# 7I92ETH.net
KiCad netlist of a schematic drawn in Altium Designer
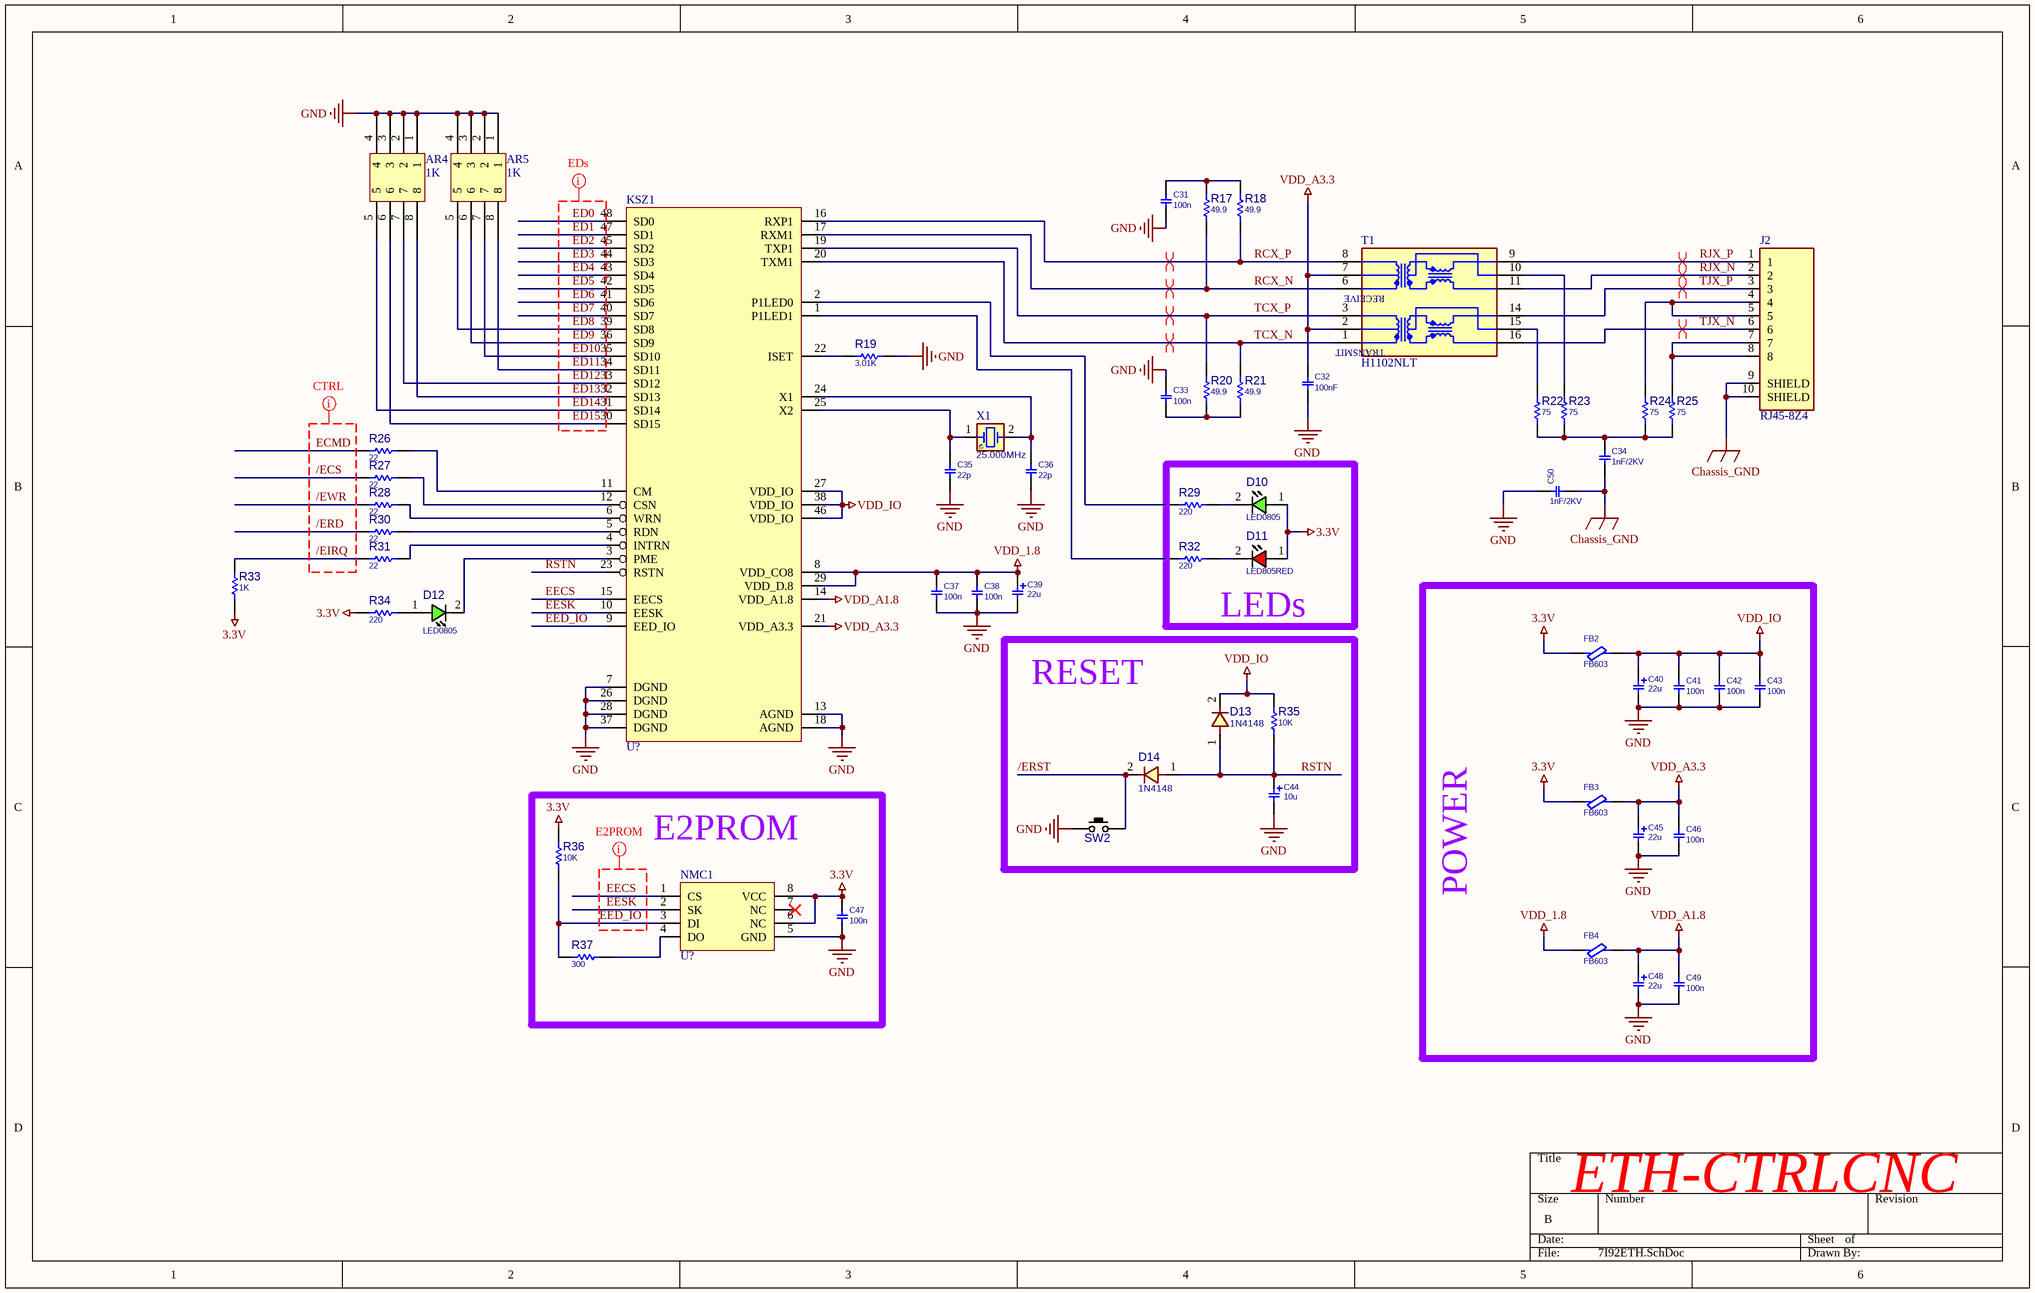
[diagram p0: 7I92ETH.SchDoc]

(export (version "E")
  (design (tool "Eeschema 10.0.6"))
  (components
    (comp (ref "AR4") (value "1K") (footprint "RP0603X4") (libsource (lib "Full_libraries") (part "ARRAY*4")))
    (comp (ref "AR5") (value "1K") (footprint "RP0603X4") (libsource (lib "Full_libraries") (part "ARRAY*4")))
    (comp (ref "C31")
      (value "100n")
      (footprint "C0603")
      (description "CAP, MLCC, 1nF, 50V, C0G, 10%, 0402")
      (fields (field (name "MANF") "Murata"))
      (libsource (lib "Full_libraries") (part "CAP_SMD_MLCC"))
    )
    (comp (ref "C32")
      (value "100nF")
      (footprint "C0603")
      (description "CAP, MLCC, 1nF, 50V, C0G, 10%, 0402")
      (fields (field (name "MANF") "Murata"))
      (libsource (lib "Full_libraries") (part "CAP_SMD_MLCC"))
    )
    (comp (ref "C33")
      (value "100n")
      (footprint "C0603")
      (description "CAP, MLCC, 1nF, 50V, C0G, 10%, 0402")
      (fields (field (name "MANF") "Murata"))
      (libsource (lib "Full_libraries") (part "CAP_SMD_MLCC"))
    )
    (comp (ref "C34")
      (value "1nF/2KV")
      (footprint "C1812")
      (description "CAP, MLCC, 1nF, 50V, C0G, 10%, 0402")
      (fields (field (name "MANF") "Murata"))
      (libsource (lib "Full_libraries") (part "CAP_SMD_MLCC"))
    )
    (comp (ref "C35")
      (value "22p")
      (footprint "C0603")
      (description "CAP, MLCC, 1nF, 50V, C0G, 10%, 0402")
      (fields (field (name "MANF") "Murata"))
      (libsource (lib "Full_libraries") (part "CAP_SMD_MLCC"))
    )
    (comp (ref "C36")
      (value "22p")
      (footprint "C0603")
      (description "CAP, MLCC, 1nF, 50V, C0G, 10%, 0402")
      (fields (field (name "MANF") "Murata"))
      (libsource (lib "Full_libraries") (part "CAP_SMD_MLCC"))
    )
    (comp (ref "C37")
      (value "100n")
      (footprint "C0603")
      (description "CAP, MLCC, 1nF, 50V, C0G, 10%, 0402")
      (fields (field (name "MANF") "Murata"))
      (libsource (lib "Full_libraries") (part "CAP_SMD_MLCC"))
    )
    (comp (ref "C38")
      (value "100n")
      (footprint "C0603")
      (description "CAP, MLCC, 1nF, 50V, C0G, 10%, 0402")
      (fields (field (name "MANF") "Murata"))
      (libsource (lib "Full_libraries") (part "CAP_SMD_MLCC"))
    )
    (comp (ref "C39")
      (value "22u")
      (footprint "C_TN_3216")
      (description "CAP, SMD, TAN,")
      (libsource (lib "Full_libraries") (part "CAP_SMD_TAN"))
    )
    (comp (ref "C40")
      (value "22u")
      (footprint "C_TN_3216")
      (description "CAP, SMD, TAN,")
      (libsource (lib "Full_libraries") (part "CAP_SMD_TAN"))
    )
    (comp (ref "C41")
      (value "100n")
      (footprint "C0603")
      (description "CAP, MLCC, 1nF, 50V, C0G, 10%, 0402")
      (fields (field (name "MANF") "Murata"))
      (libsource (lib "Full_libraries") (part "CAP_SMD_MLCC"))
    )
    (comp (ref "C42")
      (value "100n")
      (footprint "C0603")
      (description "CAP, MLCC, 1nF, 50V, C0G, 10%, 0402")
      (fields (field (name "MANF") "Murata"))
      (libsource (lib "Full_libraries") (part "CAP_SMD_MLCC"))
    )
    (comp (ref "C43")
      (value "100n")
      (footprint "C0603")
      (description "CAP, MLCC, 1nF, 50V, C0G, 10%, 0402")
      (fields (field (name "MANF") "Murata"))
      (libsource (lib "Full_libraries") (part "CAP_SMD_MLCC"))
    )
    (comp (ref "C44")
      (value "10u")
      (footprint "C_TN_3216")
      (description "CAP, SMD, TAN,")
      (libsource (lib "Full_libraries") (part "CAP_SMD_TAN"))
    )
    (comp (ref "C45")
      (value "22u")
      (footprint "C_TN_3216")
      (description "CAP, SMD, TAN,")
      (libsource (lib "Full_libraries") (part "CAP_SMD_TAN"))
    )
    (comp (ref "C46")
      (value "100n")
      (footprint "C0603")
      (description "CAP, MLCC, 1nF, 50V, C0G, 10%, 0402")
      (fields (field (name "MANF") "Murata"))
      (libsource (lib "Full_libraries") (part "CAP_SMD_MLCC"))
    )
    (comp (ref "C47")
      (value "100n")
      (footprint "C0603")
      (description "CAP, MLCC, 1nF, 50V, C0G, 10%, 0402")
      (fields (field (name "MANF") "Murata"))
      (libsource (lib "Full_libraries") (part "CAP_SMD_MLCC"))
    )
    (comp (ref "C48")
      (value "22u")
      (footprint "C_TN_3216")
      (description "CAP, SMD, TAN,")
      (libsource (lib "Full_libraries") (part "CAP_SMD_TAN"))
    )
    (comp (ref "C49")
      (value "100n")
      (footprint "C0603")
      (description "CAP, MLCC, 1nF, 50V, C0G, 10%, 0402")
      (fields (field (name "MANF") "Murata"))
      (libsource (lib "Full_libraries") (part "CAP_SMD_MLCC"))
    )
    (comp (ref "C50")
      (value "1nF/2KV")
      (footprint "C1812")
      (description "CAP, MLCC, 1nF, 50V, C0G, 10%, 0402")
      (fields (field (name "MANF") "Murata"))
      (libsource (lib "Full_libraries") (part "CAP_SMD_MLCC"))
    )
    (comp (ref "D10")
      (value "LED0805")
      (footprint "LED0805")
      (description "LED, SMD, 0805")
      (fields (field (name "MANF") "MANF") (field (name "MANF_P#") "MANF_PART#"))
      (libsource (lib "Full_libraries") (part "LED_SMD_0805"))
    )
    (comp (ref "D11")
      (value "LED805RED")
      (footprint "LED0805RED")
      (description "LED, SMD, 0805, RED")
      (fields (field (name "MANF") "MANF") (field (name "MANF_P#") "MANF_PART#"))
      (libsource (lib "Full_libraries") (part "LED_SMD_0805_RED"))
    )
    (comp (ref "D12")
      (value "LED0805")
      (footprint "LED0805")
      (description "LED, SMD, 0805")
      (fields (field (name "MANF") "MANF") (field (name "MANF_P#") "MANF_PART#"))
      (libsource (lib "Full_libraries") (part "LED_SMD_0805"))
    )
    (comp (ref "D13")
      (value "1N4148")
      (footprint "D_SOD80")
      (description "DIODE, FAST SWTICHING, 0.3A, 0.5W")
      (fields (field (name "MANF") "MANF"))
      (libsource (lib "Full_libraries") (part "DIODE_SMD_1N4148"))
    )
    (comp (ref "D14")
      (value "1N4148")
      (footprint "D_SOD80")
      (description "DIODE, FAST SWTICHING, 0.3A, 0.5W")
      (fields (field (name "MANF") "MANF"))
      (libsource (lib "Full_libraries") (part "DIODE_SMD_1N4148"))
    )
    (comp (ref "FB2")
      (value "FB603")
      (footprint "L1206")
      (description "FERRITE_Bead, SMD")
      (fields (field (name "MANF") "MURATA") (field (name "MANF_P#") "BLM15AG121SN1D"))
      (libsource (lib "Full_libraries") (part "FBEAD_SMD"))
    )
    (comp (ref "FB3")
      (value "FB603")
      (footprint "L1206")
      (description "FERRITE_Bead, SMD")
      (fields (field (name "MANF") "MURATA") (field (name "MANF_P#") "BLM15AG121SN1D"))
      (libsource (lib "Full_libraries") (part "FBEAD_SMD"))
    )
    (comp (ref "FB4")
      (value "FB603")
      (footprint "L1206")
      (description "FERRITE_Bead, SMD")
      (fields (field (name "MANF") "MURATA") (field (name "MANF_P#") "BLM15AG121SN1D"))
      (libsource (lib "Full_libraries") (part "FBEAD_SMD"))
    )
    (comp (ref "J2")
      (value "RJ45-8Z4")
      (footprint "TE_RJ45-8Z4")
      (description "CONN MOD JACK 8P8C R/A SHIELDED")
      (fields (field (name "MF") "{'manufacturer': u'TE Connectivity'}"))
      (libsource (lib "SnapEDA_Library") (part "RJ45-8Z4"))
    )
    (comp (ref "KSZ1")
      (value "U?")
      (footprint "QFG50_48")
      (description "ETHERNET IC")
      (libsource (lib "Ethernet_7i92_SchLib") (part "KSZ8851"))
    )
    (comp (ref "NMC1")
      (value "U?")
      (footprint "SO_8")
      (description "1024 BYTE ERASABLE PROGRAMABLE MEMORY")
      (libsource (lib "Ethernet_7i92_SchLib") (part "NMC9346"))
    )
    (comp (ref "R17")
      (value "49.9")
      (footprint "R0603")
      (description "RESISTOR, SMD")
      (fields (field (name "MANF_P#") "RK73H1ETTP4701F") (field (name "MANF") "KOA SPEER"))
      (libsource (lib "Full_libraries") (part "RES_SMD"))
    )
    (comp (ref "R18")
      (value "49.9")
      (footprint "R0603")
      (description "RESISTOR, SMD")
      (fields (field (name "MANF_P#") "RK73H1ETTP4701F") (field (name "MANF") "KOA SPEER"))
      (libsource (lib "Full_libraries") (part "RES_SMD"))
    )
    (comp (ref "R19")
      (value "3.01K")
      (footprint "R0805")
      (description "RESISTOR, SMD")
      (fields (field (name "MANF_P#") "RK73H1ETTP4701F") (field (name "MANF") "KOA SPEER"))
      (libsource (lib "Full_libraries") (part "RES_SMD"))
    )
    (comp (ref "R20")
      (value "49.9")
      (footprint "R0603")
      (description "RESISTOR, SMD")
      (fields (field (name "MANF_P#") "RK73H1ETTP4701F") (field (name "MANF") "KOA SPEER"))
      (libsource (lib "Full_libraries") (part "RES_SMD"))
    )
    (comp (ref "R21")
      (value "49.9")
      (footprint "R0603")
      (description "RESISTOR, SMD")
      (fields (field (name "MANF_P#") "RK73H1ETTP4701F") (field (name "MANF") "KOA SPEER"))
      (libsource (lib "Full_libraries") (part "RES_SMD"))
    )
    (comp (ref "R22")
      (value "75")
      (footprint "R0805")
      (description "RESISTOR, SMD")
      (fields (field (name "MANF_P#") "RK73H1ETTP4701F") (field (name "MANF") "KOA SPEER"))
      (libsource (lib "Full_libraries") (part "RES_SMD"))
    )
    (comp (ref "R23")
      (value "75")
      (footprint "R0805")
      (description "RESISTOR, SMD")
      (fields (field (name "MANF_P#") "RK73H1ETTP4701F") (field (name "MANF") "KOA SPEER"))
      (libsource (lib "Full_libraries") (part "RES_SMD"))
    )
    (comp (ref "R24")
      (value "75")
      (footprint "R0805")
      (description "RESISTOR, SMD")
      (fields (field (name "MANF_P#") "RK73H1ETTP4701F") (field (name "MANF") "KOA SPEER"))
      (libsource (lib "Full_libraries") (part "RES_SMD"))
    )
    (comp (ref "R25")
      (value "75")
      (footprint "R0805")
      (description "RESISTOR, SMD")
      (fields (field (name "MANF_P#") "RK73H1ETTP4701F") (field (name "MANF") "KOA SPEER"))
      (libsource (lib "Full_libraries") (part "RES_SMD"))
    )
    (comp (ref "R26")
      (value "22")
      (footprint "R0603")
      (description "RESISTOR, SMD")
      (fields (field (name "MANF_P#") "RK73H1ETTP4701F") (field (name "MANF") "KOA SPEER"))
      (libsource (lib "Full_libraries") (part "RES_SMD"))
    )
    (comp (ref "R27")
      (value "22")
      (footprint "R0603")
      (description "RESISTOR, SMD")
      (fields (field (name "MANF_P#") "RK73H1ETTP4701F") (field (name "MANF") "KOA SPEER"))
      (libsource (lib "Full_libraries") (part "RES_SMD"))
    )
    (comp (ref "R28")
      (value "22")
      (footprint "R0603")
      (description "RESISTOR, SMD")
      (fields (field (name "MANF_P#") "RK73H1ETTP4701F") (field (name "MANF") "KOA SPEER"))
      (libsource (lib "Full_libraries") (part "RES_SMD"))
    )
    (comp (ref "R29")
      (value "220")
      (footprint "R0805")
      (description "RESISTOR, SMD")
      (fields (field (name "MANF_P#") "RK73H1ETTP4701F") (field (name "MANF") "KOA SPEER"))
      (libsource (lib "Full_libraries") (part "RES_SMD"))
    )
    (comp (ref "R30")
      (value "22")
      (footprint "R0603")
      (description "RESISTOR, SMD")
      (fields (field (name "MANF_P#") "RK73H1ETTP4701F") (field (name "MANF") "KOA SPEER"))
      (libsource (lib "Full_libraries") (part "RES_SMD"))
    )
    (comp (ref "R31")
      (value "22")
      (footprint "R0603")
      (description "RESISTOR, SMD")
      (fields (field (name "MANF_P#") "RK73H1ETTP4701F") (field (name "MANF") "KOA SPEER"))
      (libsource (lib "Full_libraries") (part "RES_SMD"))
    )
    (comp (ref "R32")
      (value "220")
      (footprint "R0805")
      (description "RESISTOR, SMD")
      (fields (field (name "MANF_P#") "RK73H1ETTP4701F") (field (name "MANF") "KOA SPEER"))
      (libsource (lib "Full_libraries") (part "RES_SMD"))
    )
    (comp (ref "R33")
      (value "1K")
      (footprint "R0603")
      (description "RESISTOR, SMD")
      (fields (field (name "MANF_P#") "RK73H1ETTP4701F") (field (name "MANF") "KOA SPEER"))
      (libsource (lib "Full_libraries") (part "RES_SMD"))
    )
    (comp (ref "R34")
      (value "220")
      (footprint "R0603")
      (description "RESISTOR, SMD")
      (fields (field (name "MANF_P#") "RK73H1ETTP4701F") (field (name "MANF") "KOA SPEER"))
      (libsource (lib "Full_libraries") (part "RES_SMD"))
    )
    (comp (ref "R35")
      (value "10K")
      (footprint "R0603")
      (description "RESISTOR, SMD")
      (fields (field (name "MANF_P#") "RK73H1ETTP4701F") (field (name "MANF") "KOA SPEER"))
      (libsource (lib "Full_libraries") (part "RES_SMD"))
    )
    (comp (ref "R36")
      (value "10K")
      (footprint "R0603")
      (description "RESISTOR, SMD")
      (fields (field (name "MANF_P#") "RK73H1ETTP4701F") (field (name "MANF") "KOA SPEER"))
      (libsource (lib "Full_libraries") (part "RES_SMD"))
    )
    (comp (ref "R37")
      (value "300")
      (footprint "R0603")
      (description "RESISTOR, SMD")
      (fields (field (name "MANF_P#") "RK73H1ETTP4701F") (field (name "MANF") "KOA SPEER"))
      (libsource (lib "Full_libraries") (part "RES_SMD"))
    )
    (comp (ref "SW2")
      (value "PUSHBUTTON")
      (footprint "SWPBS_SPST_6X3X5")
      (description "SWITCH, PUSH BUTTON, TACTILE, SMD, SPST, 6X3.5X4.3mm")
      (fields (field (name "MANF") "Panasonic") (field (name "MANF_P#") "EVQ-PNF04M"))
      (libsource (lib "Full_libraries") (part "SWPBS_SPST_6X3X4"))
    )
    (comp (ref "T1")
      (value "H1102NLT")
      (footprint "XFMR_H1102NLT")
      (description "Telecom Transformer 1: 1/1: 1 0.65Ohm Prim. DCR 0.65Ohm Sec. DCR 16Term. Gull Wing SMD")
      (fields (field (name "MF") "{'manufacturer': u'Pulse Electronics Network'}"))
      (libsource (lib "SnapEDA_Library") (part "H1102NLT"))
    )
    (comp (ref "X1")
      (value "25.000MHz")
      (footprint "XTLT_2")
      (description "Crystal MOST POPULAR ABL HC49 PACKAGE")
      (libsource (lib "Full_libraries") (part "XTL_2_HC49_THD"))
    )
  )
  (nets
    (net (code "1") (name "/ECMD") (class "Default")
      (node (ref "R26") (pin "2") (pinfunction "2_2") (pintype "passive"))
    )
    (net (code "2") (name "/ED0") (class "Default")
      (node (ref "KSZ1") (pin "48") (pinfunction "SD0_48") (pintype "passive"))
    )
    (net (code "3") (name "/ED1") (class "Default")
      (node (ref "KSZ1") (pin "47") (pinfunction "SD1_47") (pintype "passive"))
    )
    (net (code "4") (name "/ED2") (class "Default")
      (node (ref "KSZ1") (pin "45") (pinfunction "SD2_45") (pintype "passive"))
    )
    (net (code "5") (name "/ED3") (class "Default")
      (node (ref "KSZ1") (pin "44") (pinfunction "SD3_44") (pintype "passive"))
    )
    (net (code "6") (name "/ED4") (class "Default")
      (node (ref "KSZ1") (pin "43") (pinfunction "SD4_43") (pintype "passive"))
    )
    (net (code "7") (name "/ED5") (class "Default")
      (node (ref "KSZ1") (pin "42") (pinfunction "SD5_42") (pintype "passive"))
    )
    (net (code "8") (name "/ED6") (class "Default")
      (node (ref "KSZ1") (pin "41") (pinfunction "SD6_41") (pintype "passive"))
    )
    (net (code "9") (name "/ED7") (class "Default")
      (node (ref "KSZ1") (pin "40") (pinfunction "SD7_40") (pintype "passive"))
    )
    (net (code "10") (name "/ED8") (class "Default")
      (node (ref "AR5") (pin "5") (pinfunction "5_5") (pintype "passive"))
      (node (ref "KSZ1") (pin "39") (pinfunction "SD8_39") (pintype "passive"))
    )
    (net (code "11") (name "/ED9") (class "Default")
      (node (ref "AR5") (pin "6") (pinfunction "6_6") (pintype "passive"))
      (node (ref "KSZ1") (pin "36") (pinfunction "SD9_36") (pintype "passive"))
    )
    (net (code "12") (name "/ED10") (class "Default")
      (node (ref "AR5") (pin "7") (pinfunction "7_7") (pintype "passive"))
      (node (ref "KSZ1") (pin "35") (pinfunction "SD10_35") (pintype "passive"))
    )
    (net (code "13") (name "/ED11") (class "Default")
      (node (ref "AR5") (pin "8") (pinfunction "8_8") (pintype "passive"))
      (node (ref "KSZ1") (pin "34") (pinfunction "SD11_34") (pintype "passive"))
    )
    (net (code "14") (name "/ED12") (class "Default")
      (node (ref "AR4") (pin "7") (pinfunction "7_7") (pintype "passive"))
      (node (ref "KSZ1") (pin "33") (pinfunction "SD12_33") (pintype "passive"))
    )
    (net (code "15") (name "/ED13") (class "Default")
      (node (ref "AR4") (pin "8") (pinfunction "8_8") (pintype "passive"))
      (node (ref "KSZ1") (pin "32") (pinfunction "SD13_32") (pintype "passive"))
    )
    (net (code "16") (name "/ED14") (class "Default")
      (node (ref "AR4") (pin "5") (pinfunction "5_5") (pintype "passive"))
      (node (ref "KSZ1") (pin "31") (pinfunction "SD14_31") (pintype "passive"))
    )
    (net (code "17") (name "/ED15") (class "Default")
      (node (ref "AR4") (pin "6") (pinfunction "6_6") (pintype "passive"))
      (node (ref "KSZ1") (pin "30") (pinfunction "SD15_30") (pintype "passive"))
    )
    (net (code "18") (name "/EECS") (class "Default")
      (node (ref "KSZ1") (pin "15") (pinfunction "EECS_15") (pintype "passive"))
      (node (ref "NMC1") (pin "1") (pinfunction "CS_1") (pintype "passive"))
    )
    (net (code "19") (name "/EED_IO") (class "Default")
      (node (ref "KSZ1") (pin "9") (pinfunction "EED_IO_9") (pintype "passive"))
      (node (ref "NMC1") (pin "3") (pinfunction "DI_3") (pintype "passive"))
      (node (ref "R36") (pin "2") (pinfunction "2_2") (pintype "passive"))
      (node (ref "R37") (pin "1") (pinfunction "1_1") (pintype "passive"))
    )
    (net (code "20") (name "/EESK") (class "Default")
      (node (ref "KSZ1") (pin "10") (pinfunction "EESK_10") (pintype "passive"))
      (node (ref "NMC1") (pin "2") (pinfunction "SK_2") (pintype "passive"))
    )
    (net (code "21") (name "/RCX_N") (class "Default")
      (node (ref "KSZ1") (pin "17") (pinfunction "RXM1_17") (pintype "passive"))
      (node (ref "R17") (pin "1") (pinfunction "1_1") (pintype "passive"))
      (node (ref "T1") (pin "6") (pinfunction "6_6") (pintype "passive"))
    )
    (net (code "22") (name "/RCX_P") (class "Default")
      (node (ref "KSZ1") (pin "16") (pinfunction "RXP1_16") (pintype "passive"))
      (node (ref "R18") (pin "1") (pinfunction "1_1") (pintype "passive"))
      (node (ref "T1") (pin "8") (pinfunction "8_8") (pintype "passive"))
    )
    (net (code "23") (name "/RJX_N") (class "Default")
      (node (ref "J2") (pin "2") (pinfunction "2_2") (pintype "passive"))
      (node (ref "T1") (pin "11") (pinfunction "11_11") (pintype "passive"))
    )
    (net (code "24") (name "/RJX_P") (class "Default")
      (node (ref "J2") (pin "1") (pinfunction "1_1") (pintype "passive"))
      (node (ref "T1") (pin "9") (pinfunction "9_9") (pintype "passive"))
    )
    (net (code "25") (name "/RSTN") (class "Default")
      (node (ref "C44") (pin "1") (pinfunction "1_1") (pintype "passive"))
      (node (ref "D13") (pin "1") (pinfunction "1_1") (pintype "passive"))
      (node (ref "D14") (pin "1") (pinfunction "1_1") (pintype "passive"))
      (node (ref "KSZ1") (pin "23") (pinfunction "RSTN_23") (pintype "passive"))
      (node (ref "R35") (pin "1") (pinfunction "1_1") (pintype "passive"))
    )
    (net (code "26") (name "/TCX_N") (class "Default")
      (node (ref "KSZ1") (pin "20") (pinfunction "TXM1_20") (pintype "passive"))
      (node (ref "R21") (pin "2") (pinfunction "2_2") (pintype "passive"))
      (node (ref "T1") (pin "1") (pinfunction "1_1") (pintype "passive"))
    )
    (net (code "27") (name "/TCX_P") (class "Default")
      (node (ref "KSZ1") (pin "19") (pinfunction "TXP1_19") (pintype "passive"))
      (node (ref "R20") (pin "2") (pinfunction "2_2") (pintype "passive"))
      (node (ref "T1") (pin "3") (pinfunction "3_3") (pintype "passive"))
    )
    (net (code "28") (name "/TJX_N") (class "Default")
      (node (ref "J2") (pin "6") (pinfunction "6_6") (pintype "passive"))
      (node (ref "T1") (pin "16") (pinfunction "16_16") (pintype "passive"))
    )
    (net (code "29") (name "/TJX_P") (class "Default")
      (node (ref "J2") (pin "3") (pinfunction "3_3") (pintype "passive"))
      (node (ref "T1") (pin "14") (pinfunction "14_14") (pintype "passive"))
    )
    (net (code "30") (name "/{slash}ECS") (class "Default")
      (node (ref "R27") (pin "2") (pinfunction "2_2") (pintype "passive"))
    )
    (net (code "31") (name "/{slash}EIRQ") (class "Default")
      (node (ref "R31") (pin "2") (pinfunction "2_2") (pintype "passive"))
      (node (ref "R33") (pin "1") (pinfunction "1_1") (pintype "passive"))
    )
    (net (code "32") (name "/{slash}ERD") (class "Default")
      (node (ref "R30") (pin "2") (pinfunction "2_2") (pintype "passive"))
    )
    (net (code "33") (name "/{slash}ERST") (class "Default")
      (node (ref "D14") (pin "2") (pinfunction "2_2") (pintype "passive"))
      (node (ref "SW2") (pin "2") (pinfunction "P3_2") (pintype "passive"))
    )
    (net (code "34") (name "/{slash}EWR") (class "Default")
      (node (ref "R28") (pin "2") (pinfunction "2_2") (pintype "passive"))
    )
    (net (code "35") (name "3.3V") (class "Default")
      (node (ref "C47") (pin "1") (pinfunction "1_1") (pintype "passive"))
      (node (ref "D10") (pin "1") (pinfunction "ANODE_1") (pintype "passive"))
      (node (ref "D11") (pin "1") (pinfunction "ANODE_1") (pintype "passive"))
      (node (ref "FB2") (pin "1") (pinfunction "1_1") (pintype "passive"))
      (node (ref "FB3") (pin "1") (pinfunction "1_1") (pintype "passive"))
      (node (ref "NMC1") (pin "6") (pinfunction "NC_6") (pintype "passive"))
      (node (ref "NMC1") (pin "8") (pinfunction "VCC_8") (pintype "passive"))
      (node (ref "R33") (pin "2") (pinfunction "2_2") (pintype "passive"))
      (node (ref "R34") (pin "2") (pinfunction "2_2") (pintype "passive"))
      (node (ref "R36") (pin "1") (pinfunction "1_1") (pintype "passive"))
    )
    (net (code "36") (name "Chassis_GND") (class "Default")
      (node (ref "C34") (pin "2") (pinfunction "2_2") (pintype "passive"))
      (node (ref "C50") (pin "2") (pinfunction "2_2") (pintype "passive"))
      (node (ref "J2") (pin "10") (pinfunction "SHIELD_10") (pintype "passive"))
      (node (ref "J2") (pin "9") (pinfunction "SHIELD_9") (pintype "passive"))
    )
    (net (code "37") (name "GND") (class "Default")
      (node (ref "AR4") (pin "1") (pinfunction "1_1") (pintype "passive"))
      (node (ref "AR4") (pin "2") (pinfunction "2_2") (pintype "passive"))
      (node (ref "AR4") (pin "3") (pinfunction "3_3") (pintype "passive"))
      (node (ref "AR4") (pin "4") (pinfunction "4_4") (pintype "passive"))
      (node (ref "AR5") (pin "1") (pinfunction "1_1") (pintype "passive"))
      (node (ref "AR5") (pin "2") (pinfunction "2_2") (pintype "passive"))
      (node (ref "AR5") (pin "3") (pinfunction "3_3") (pintype "passive"))
      (node (ref "AR5") (pin "4") (pinfunction "4_4") (pintype "passive"))
      (node (ref "C31") (pin "2") (pinfunction "2_2") (pintype "passive"))
      (node (ref "C32") (pin "2") (pinfunction "2_2") (pintype "passive"))
      (node (ref "C33") (pin "1") (pinfunction "1_1") (pintype "passive"))
      (node (ref "C35") (pin "2") (pinfunction "2_2") (pintype "passive"))
      (node (ref "C36") (pin "2") (pinfunction "2_2") (pintype "passive"))
      (node (ref "C37") (pin "2") (pinfunction "2_2") (pintype "passive"))
      (node (ref "C38") (pin "2") (pinfunction "2_2") (pintype "passive"))
      (node (ref "C39") (pin "2") (pinfunction "2_2") (pintype "passive"))
      (node (ref "C40") (pin "2") (pinfunction "2_2") (pintype "passive"))
      (node (ref "C41") (pin "2") (pinfunction "2_2") (pintype "passive"))
      (node (ref "C42") (pin "2") (pinfunction "2_2") (pintype "passive"))
      (node (ref "C43") (pin "2") (pinfunction "2_2") (pintype "passive"))
      (node (ref "C44") (pin "2") (pinfunction "2_2") (pintype "passive"))
      (node (ref "C45") (pin "2") (pinfunction "2_2") (pintype "passive"))
      (node (ref "C46") (pin "2") (pinfunction "2_2") (pintype "passive"))
      (node (ref "C47") (pin "2") (pinfunction "2_2") (pintype "passive"))
      (node (ref "C48") (pin "2") (pinfunction "2_2") (pintype "passive"))
      (node (ref "C49") (pin "2") (pinfunction "2_2") (pintype "passive"))
      (node (ref "C50") (pin "1") (pinfunction "1_1") (pintype "passive"))
      (node (ref "KSZ1") (pin "13") (pinfunction "AGND_13") (pintype "passive"))
      (node (ref "KSZ1") (pin "18") (pinfunction "AGND_18") (pintype "passive"))
      (node (ref "KSZ1") (pin "26") (pinfunction "DGND_26") (pintype "passive"))
      (node (ref "KSZ1") (pin "28") (pinfunction "DGND_28") (pintype "passive"))
      (node (ref "KSZ1") (pin "37") (pinfunction "DGND_37") (pintype "passive"))
      (node (ref "KSZ1") (pin "7") (pinfunction "DGND_7") (pintype "passive"))
      (node (ref "NMC1") (pin "5") (pinfunction "GND_5") (pintype "passive"))
      (node (ref "R19") (pin "1") (pinfunction "1_1") (pintype "passive"))
      (node (ref "SW2") (pin "1") (pinfunction "P1_1") (pintype "passive"))
    )
    (net (code "38") (name "Net-(C31-Pad1)") (class "Default")
      (node (ref "C31") (pin "1") (pinfunction "1_1") (pintype "passive"))
      (node (ref "R17") (pin "2") (pinfunction "2_2") (pintype "passive"))
      (node (ref "R18") (pin "2") (pinfunction "2_2") (pintype "passive"))
    )
    (net (code "39") (name "Net-(C33-Pad2)") (class "Default")
      (node (ref "C33") (pin "2") (pinfunction "2_2") (pintype "passive"))
      (node (ref "R20") (pin "1") (pinfunction "1_1") (pintype "passive"))
      (node (ref "R21") (pin "1") (pinfunction "1_1") (pintype "passive"))
    )
    (net (code "40") (name "Net-(C34-Pad1)") (class "Default")
      (node (ref "C34") (pin "1") (pinfunction "1_1") (pintype "passive"))
      (node (ref "R22") (pin "1") (pinfunction "1_1") (pintype "passive"))
      (node (ref "R23") (pin "1") (pinfunction "1_1") (pintype "passive"))
      (node (ref "R24") (pin "1") (pinfunction "1_1") (pintype "passive"))
      (node (ref "R25") (pin "1") (pinfunction "1_1") (pintype "passive"))
    )
    (net (code "41") (name "Net-(D10-CATHODE)") (class "Default")
      (node (ref "D10") (pin "2") (pinfunction "CATHODE_2") (pintype "passive"))
      (node (ref "R29") (pin "1") (pinfunction "1_1") (pintype "passive"))
    )
    (net (code "42") (name "Net-(D11-CATHODE)") (class "Default")
      (node (ref "D11") (pin "2") (pinfunction "CATHODE_2") (pintype "passive"))
      (node (ref "R32") (pin "1") (pinfunction "1_1") (pintype "passive"))
    )
    (net (code "43") (name "Net-(D12-ANODE)") (class "Default")
      (node (ref "D12") (pin "1") (pinfunction "ANODE_1") (pintype "passive"))
      (node (ref "R34") (pin "1") (pinfunction "1_1") (pintype "passive"))
    )
    (net (code "44") (name "Net-(D12-CATHODE)") (class "Default")
      (node (ref "D12") (pin "2") (pinfunction "CATHODE_2") (pintype "passive"))
      (node (ref "KSZ1") (pin "3") (pinfunction "PME_3") (pintype "passive"))
    )
    (net (code "45") (name "Net-(J2-Pad4)") (class "Default")
      (node (ref "J2") (pin "4") (pinfunction "4_4") (pintype "passive"))
      (node (ref "J2") (pin "5") (pinfunction "5_5") (pintype "passive"))
      (node (ref "R24") (pin "2") (pinfunction "2_2") (pintype "passive"))
    )
    (net (code "46") (name "Net-(J2-Pad7)") (class "Default")
      (node (ref "J2") (pin "7") (pinfunction "7_7") (pintype "passive"))
      (node (ref "J2") (pin "8") (pinfunction "8_8") (pintype "passive"))
      (node (ref "R25") (pin "2") (pinfunction "2_2") (pintype "passive"))
    )
    (net (code "47") (name "Net-(KSZ1-CM)") (class "Default")
      (node (ref "KSZ1") (pin "11") (pinfunction "CM_11") (pintype "passive"))
      (node (ref "R26") (pin "1") (pinfunction "1_1") (pintype "passive"))
    )
    (net (code "48") (name "Net-(KSZ1-CSN)") (class "Default")
      (node (ref "KSZ1") (pin "12") (pinfunction "CSN_12") (pintype "passive"))
      (node (ref "R27") (pin "1") (pinfunction "1_1") (pintype "passive"))
    )
    (net (code "49") (name "Net-(KSZ1-INTRN)") (class "Default")
      (node (ref "KSZ1") (pin "4") (pinfunction "INTRN_4") (pintype "passive"))
      (node (ref "R31") (pin "1") (pinfunction "1_1") (pintype "passive"))
    )
    (net (code "50") (name "Net-(KSZ1-ISET)") (class "Default")
      (node (ref "KSZ1") (pin "22") (pinfunction "ISET_22") (pintype "passive"))
      (node (ref "R19") (pin "2") (pinfunction "2_2") (pintype "passive"))
    )
    (net (code "51") (name "Net-(KSZ1-P1LED0)") (class "Default")
      (node (ref "KSZ1") (pin "2") (pinfunction "P1LED0_2") (pintype "passive"))
      (node (ref "R29") (pin "2") (pinfunction "2_2") (pintype "passive"))
    )
    (net (code "52") (name "Net-(KSZ1-P1LED1)") (class "Default")
      (node (ref "KSZ1") (pin "1") (pinfunction "P1LED1_1") (pintype "passive"))
      (node (ref "R32") (pin "2") (pinfunction "2_2") (pintype "passive"))
    )
    (net (code "53") (name "Net-(KSZ1-RDN)") (class "Default")
      (node (ref "KSZ1") (pin "5") (pinfunction "RDN_5") (pintype "passive"))
      (node (ref "R30") (pin "1") (pinfunction "1_1") (pintype "passive"))
    )
    (net (code "54") (name "Net-(KSZ1-WRN)") (class "Default")
      (node (ref "KSZ1") (pin "6") (pinfunction "WRN_6") (pintype "passive"))
      (node (ref "R28") (pin "1") (pinfunction "1_1") (pintype "passive"))
    )
    (net (code "55") (name "Net-(KSZ1-X1)") (class "Default")
      (node (ref "C36") (pin "1") (pinfunction "1_1") (pintype "passive"))
      (node (ref "KSZ1") (pin "24") (pinfunction "X1_24") (pintype "passive"))
      (node (ref "X1") (pin "2") (pinfunction "OSC2_2") (pintype "passive"))
    )
    (net (code "56") (name "Net-(KSZ1-X2)") (class "Default")
      (node (ref "C35") (pin "1") (pinfunction "1_1") (pintype "passive"))
      (node (ref "KSZ1") (pin "25") (pinfunction "X2_25") (pintype "passive"))
      (node (ref "X1") (pin "1") (pinfunction "OSC1_1") (pintype "passive"))
    )
    (net (code "57") (name "Net-(NMC1-DO)") (class "Default")
      (node (ref "NMC1") (pin "4") (pinfunction "DO_4") (pintype "passive"))
      (node (ref "R37") (pin "2") (pinfunction "2_2") (pintype "passive"))
    )
    (net (code "58") (name "Net-(R22-Pad2)") (class "Default")
      (node (ref "R22") (pin "2") (pinfunction "2_2") (pintype "passive"))
      (node (ref "T1") (pin "15") (pinfunction "15_15") (pintype "passive"))
    )
    (net (code "59") (name "Net-(R23-Pad2)") (class "Default")
      (node (ref "R23") (pin "2") (pinfunction "2_2") (pintype "passive"))
      (node (ref "T1") (pin "10") (pinfunction "10_10") (pintype "passive"))
    )
    (net (code "60") (name "VDD_1.8") (class "Default")
      (node (ref "C37") (pin "1") (pinfunction "1_1") (pintype "passive"))
      (node (ref "C38") (pin "1") (pinfunction "1_1") (pintype "passive"))
      (node (ref "C39") (pin "1") (pinfunction "1_1") (pintype "passive"))
      (node (ref "FB4") (pin "1") (pinfunction "1_1") (pintype "passive"))
      (node (ref "KSZ1") (pin "29") (pinfunction "VDD_D.8_29") (pintype "passive"))
      (node (ref "KSZ1") (pin "8") (pinfunction "VDD_CO8_8") (pintype "passive"))
    )
    (net (code "61") (name "VDD_A1.8") (class "Default")
      (node (ref "C48") (pin "1") (pinfunction "1_1") (pintype "passive"))
      (node (ref "C49") (pin "1") (pinfunction "1_1") (pintype "passive"))
      (node (ref "FB4") (pin "2") (pinfunction "2_2") (pintype "passive"))
      (node (ref "KSZ1") (pin "14") (pinfunction "VDD_A1.8_14") (pintype "passive"))
    )
    (net (code "62") (name "VDD_A3.3") (class "Default")
      (node (ref "C32") (pin "1") (pinfunction "1_1") (pintype "passive"))
      (node (ref "C45") (pin "1") (pinfunction "1_1") (pintype "passive"))
      (node (ref "C46") (pin "1") (pinfunction "1_1") (pintype "passive"))
      (node (ref "FB3") (pin "2") (pinfunction "2_2") (pintype "passive"))
      (node (ref "KSZ1") (pin "21") (pinfunction "VDD_A3.3_21") (pintype "passive"))
      (node (ref "T1") (pin "2") (pinfunction "2_2") (pintype "passive"))
      (node (ref "T1") (pin "7") (pinfunction "7_7") (pintype "passive"))
    )
    (net (code "63") (name "VDD_IO") (class "Default")
      (node (ref "C40") (pin "1") (pinfunction "1_1") (pintype "passive"))
      (node (ref "C41") (pin "1") (pinfunction "1_1") (pintype "passive"))
      (node (ref "C42") (pin "1") (pinfunction "1_1") (pintype "passive"))
      (node (ref "C43") (pin "1") (pinfunction "1_1") (pintype "passive"))
      (node (ref "D13") (pin "2") (pinfunction "2_2") (pintype "passive"))
      (node (ref "FB2") (pin "2") (pinfunction "2_2") (pintype "passive"))
      (node (ref "KSZ1") (pin "27") (pinfunction "VDD_IO_27") (pintype "passive"))
      (node (ref "KSZ1") (pin "38") (pinfunction "VDD_IO_38") (pintype "passive"))
      (node (ref "KSZ1") (pin "46") (pinfunction "VDD_IO_46") (pintype "passive"))
      (node (ref "R35") (pin "2") (pinfunction "2_2") (pintype "passive"))
    )
    (net (code "64") (name "unconnected-(NMC1-NC-Pad7)") (class "Default")
      (node (ref "NMC1") (pin "7") (pinfunction "NC_7") (pintype "passive+no_connect"))
    )
  )
)
